# 2A_Regulation_board.net
KiCad netlist of a schematic drawn in EAGLE
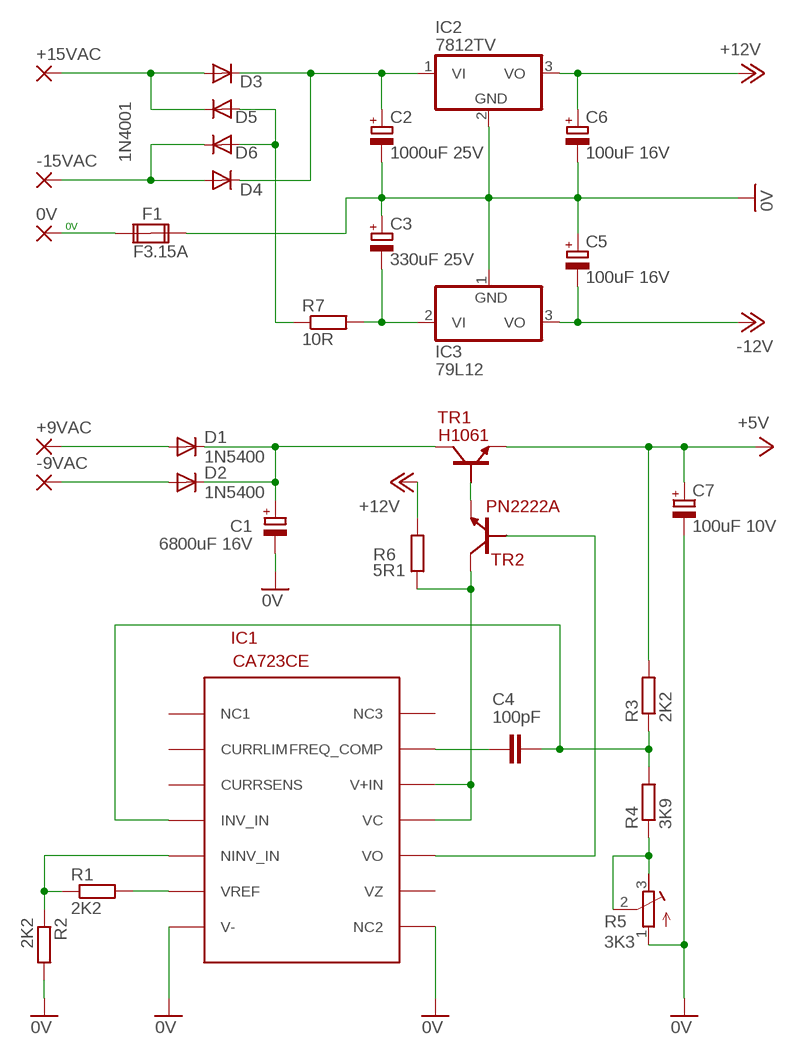
[diagram p0: schematic, sheet 1]

(export (version "E")
  (design (tool "Eeschema 10.0.6"))
  (components
    (comp (ref "+9VAC")
      (value "3,81/1,4")
      (footprint "eagle-import:3,81_1,4")
      (libsource (lib "eagle-import") (part "3,81/1,4"))
    )
    (comp (ref "+15VAC")
      (value "3,81/1,4")
      (footprint "eagle-import:3,81_1,4")
      (libsource (lib "eagle-import") (part "3,81/1,4"))
    )
    (comp (ref "-9VAC")
      (value "3,81/1,4")
      (footprint "eagle-import:3,81_1,4")
      (libsource (lib "eagle-import") (part "3,81/1,4"))
    )
    (comp (ref "-15VAC")
      (value "3,81/1,4")
      (footprint "eagle-import:3,81_1,4")
      (libsource (lib "eagle-import") (part "3,81/1,4"))
    )
    (comp (ref "0V")
      (value "3,81/1,4")
      (footprint "eagle-import:3,81_1,4")
      (libsource (lib "eagle-import") (part "3,81/1,4"))
    )
    (comp (ref "C1")
      (value "6800uF 16V")
      (footprint "eagle-import:E7,5-16")
      (libsource (lib "eagle-import") (part "CPOL-EUE7.5-16"))
    )
    (comp (ref "C2")
      (value "1000uF 25V")
      (footprint "eagle-import:E5-13")
      (libsource (lib "eagle-import") (part "CPOL-EUE5-13"))
    )
    (comp (ref "C3")
      (value "330uF 25V")
      (footprint "eagle-import:E5-10,5")
      (libsource (lib "eagle-import") (part "CPOL-EUE5-10.5"))
    )
    (comp (ref "C4")
      (value "100pF")
      (footprint "eagle-import:C025-025X050")
      (libsource (lib "eagle-import") (part "C-EU025-025X050"))
    )
    (comp (ref "C5")
      (value "100uF 16V")
      (footprint "eagle-import:E2,5-6")
      (libsource (lib "eagle-import") (part "CPOL-EUE2.5-6"))
    )
    (comp (ref "C6")
      (value "100uF 16V")
      (footprint "eagle-import:E2,5-6")
      (libsource (lib "eagle-import") (part "CPOL-EUE2.5-6"))
    )
    (comp (ref "C7")
      (value "100uF 10V")
      (footprint "eagle-import:E2-5")
      (libsource (lib "eagle-import") (part "CPOL-EUE2-5"))
    )
    (comp (ref "D1")
      (value "1N5400")
      (footprint "eagle-import:DO201-15")
      (libsource (lib "eagle-import") (part "1N5400"))
    )
    (comp (ref "D2")
      (value "1N5400")
      (footprint "eagle-import:DO201-15")
      (libsource (lib "eagle-import") (part "1N5400"))
    )
    (comp (ref "D3")
      (value "1N4001")
      (footprint "eagle-import:DO41-10")
      (libsource (lib "eagle-import") (part "1N4004"))
    )
    (comp (ref "D4")
      (value "1N4001")
      (footprint "eagle-import:DO41-10")
      (libsource (lib "eagle-import") (part "1N4004"))
    )
    (comp (ref "D5")
      (value "1N4001")
      (footprint "eagle-import:DO41-10")
      (libsource (lib "eagle-import") (part "1N4004"))
    )
    (comp (ref "D6")
      (value "1N4001")
      (footprint "eagle-import:DO41-10")
      (libsource (lib "eagle-import") (part "1N4004"))
    )
    (comp (ref "F1")
      (value "F3.15A")
      (footprint "eagle-import:FUSE1")
      (libsource (lib "eagle-import") (part "FUSE2P"))
    )
    (comp (ref "IC1")
      (value "CA723CE")
      (footprint "eagle-import:PDIP-14")
      (libsource (lib "eagle-import") (part "CA723CA-PDIP"))
    )
    (comp (ref "IC2")
      (value "7812TV")
      (footprint "eagle-import:TO220V")
      (libsource (lib "eagle-import") (part "78TV12"))
    )
    (comp (ref "IC3")
      (value "79L12")
      (footprint "eagle-import:TO92")
      (libsource (lib "eagle-import") (part "79L12"))
    )
    (comp (ref "R1")
      (value "2K2")
      (footprint "eagle-import:0207_10")
      (libsource (lib "eagle-import") (part "R-EU_0207/10"))
    )
    (comp (ref "R2")
      (value "2K2")
      (footprint "eagle-import:0207_10")
      (libsource (lib "eagle-import") (part "R-EU_0207/10"))
    )
    (comp (ref "R3")
      (value "2K2")
      (footprint "eagle-import:0207_10")
      (libsource (lib "eagle-import") (part "R-EU_0207/10"))
    )
    (comp (ref "R4")
      (value "3K9")
      (footprint "eagle-import:0207_10")
      (libsource (lib "eagle-import") (part "R-EU_0207/10"))
    )
    (comp (ref "R5")
      (value "3K3")
      (footprint "eagle-import:RTRIM3339P")
      (libsource (lib "eagle-import") (part "R-TRIMM3339P"))
    )
    (comp (ref "R6")
      (value "5R1")
      (footprint "eagle-import:0207_15")
      (libsource (lib "eagle-import") (part "R-EU_0207/15"))
    )
    (comp (ref "R7")
      (value "10R")
      (footprint "eagle-import:0309_10")
      (libsource (lib "eagle-import") (part "R-EU_0309/10"))
    )
    (comp (ref "TR1")
      (value "H1061")
      (footprint "eagle-import:TO220AB")
      (libsource (lib "eagle-import") (part "H1061"))
    )
    (comp (ref "TR2")
      (value "PN2222A")
      (footprint "eagle-import:TO-92")
      (libsource (lib "eagle-import") (part "PN2222A"))
    )
  )
  (nets
    (net (code "1") (name "+5V") (class "Default")
      (node (ref "C7") (pin "+") (pinfunction "+_+") (pintype "passive"))
      (node (ref "R3") (pin "2") (pinfunction "2_2") (pintype "passive"))
      (node (ref "TR1") (pin "E") (pinfunction "E_E") (pintype "bidirectional"))
    )
    (net (code "2") (name "+12V") (class "Default")
      (node (ref "C6") (pin "+") (pinfunction "+_+") (pintype "passive"))
      (node (ref "IC2") (pin "3") (pinfunction "VO_3") (pintype "passive"))
      (node (ref "R6") (pin "2") (pinfunction "2_2") (pintype "passive"))
    )
    (net (code "3") (name "-12V") (class "Default")
      (node (ref "C5") (pin "-") (pinfunction "-_-") (pintype "passive"))
      (node (ref "IC3") (pin "3") (pinfunction "VO_3") (pintype "passive"))
    )
    (net (code "4") (name "0V") (class "Default")
      (node (ref "C1") (pin "-") (pinfunction "-_-") (pintype "passive"))
      (node (ref "C2") (pin "-") (pinfunction "-_-") (pintype "passive"))
      (node (ref "C3") (pin "+") (pinfunction "+_+") (pintype "passive"))
      (node (ref "C5") (pin "+") (pinfunction "+_+") (pintype "passive"))
      (node (ref "C6") (pin "-") (pinfunction "-_-") (pintype "passive"))
      (node (ref "C7") (pin "-") (pinfunction "-_-") (pintype "passive"))
      (node (ref "F1") (pin "2A") (pinfunction "2A_2A") (pintype "passive"))
      (node (ref "IC1") (pin "NC2") (pinfunction "NC2_NC2") (pintype "bidirectional"))
      (node (ref "IC1") (pin "V-") (pinfunction "V-_V-") (pintype "bidirectional"))
      (node (ref "IC2") (pin "2") (pinfunction "GND_2") (pintype "passive"))
      (node (ref "IC3") (pin "1") (pinfunction "GND_1") (pintype "passive"))
      (node (ref "R2") (pin "2") (pinfunction "2_2") (pintype "passive"))
      (node (ref "R5") (pin "1") (pinfunction "E_1") (pintype "passive"))
    )
    (net (code "5") (name "Net-(+9VAC-P)") (class "Default")
      (node (ref "+9VAC") (pin "1") (pinfunction "P_1") (pintype "passive"))
      (node (ref "D1") (pin "A") (pinfunction "A_A") (pintype "passive"))
    )
    (net (code "6") (name "Net-(+15VAC-P)") (class "Default")
      (node (ref "+15VAC") (pin "1") (pinfunction "P_1") (pintype "passive"))
      (node (ref "D3") (pin "A") (pinfunction "A_A") (pintype "passive"))
      (node (ref "D5") (pin "C") (pinfunction "C_C") (pintype "passive"))
    )
    (net (code "7") (name "Net-(-9VAC-P)") (class "Default")
      (node (ref "-9VAC") (pin "1") (pinfunction "P_1") (pintype "passive"))
      (node (ref "D2") (pin "A") (pinfunction "A_A") (pintype "passive"))
    )
    (net (code "8") (name "Net-(-15VAC-P)") (class "Default")
      (node (ref "-15VAC") (pin "1") (pinfunction "P_1") (pintype "passive"))
      (node (ref "D4") (pin "A") (pinfunction "A_A") (pintype "passive"))
      (node (ref "D6") (pin "C") (pinfunction "C_C") (pintype "passive"))
    )
    (net (code "9") (name "Net-(0V-P)") (class "Default")
      (node (ref "0V") (pin "1") (pinfunction "P_1") (pintype "passive"))
      (node (ref "F1") (pin "1A") (pinfunction "1A_1A") (pintype "passive"))
    )
    (net (code "10") (name "Net-(C1-Pad+)") (class "Default")
      (node (ref "C1") (pin "+") (pinfunction "+_+") (pintype "passive"))
      (node (ref "D1") (pin "C") (pinfunction "C_C") (pintype "passive"))
      (node (ref "D2") (pin "C") (pinfunction "C_C") (pintype "passive"))
      (node (ref "TR1") (pin "C") (pinfunction "C_C") (pintype "bidirectional"))
    )
    (net (code "11") (name "Net-(C4-Pad1)") (class "Default")
      (node (ref "C4") (pin "1") (pinfunction "1_1") (pintype "passive"))
      (node (ref "IC1") (pin "FREQ_COMP") (pinfunction "FREQ_COMP_FREQ_COMP") (pintype "bidirectional"))
    )
    (net (code "12") (name "Net-(D5-PadA)") (class "Default")
      (node (ref "D5") (pin "A") (pinfunction "A_A") (pintype "passive"))
      (node (ref "D6") (pin "A") (pinfunction "A_A") (pintype "passive"))
      (node (ref "R7") (pin "1") (pinfunction "1_1") (pintype "passive"))
    )
    (net (code "13") (name "Net-(IC1-INV_IN)") (class "Default")
      (node (ref "C4") (pin "2") (pinfunction "2_2") (pintype "passive"))
      (node (ref "IC1") (pin "INV_INP") (pinfunction "INV_IN_INV_INP") (pintype "bidirectional"))
      (node (ref "R3") (pin "1") (pinfunction "1_1") (pintype "passive"))
      (node (ref "R4") (pin "2") (pinfunction "2_2") (pintype "passive"))
    )
    (net (code "14") (name "Net-(IC1-NINV_IN)") (class "Default")
      (node (ref "IC1") (pin "NINV_INP") (pinfunction "NINV_IN_NINV_INP") (pintype "bidirectional"))
      (node (ref "R1") (pin "1") (pinfunction "1_1") (pintype "passive"))
      (node (ref "R2") (pin "1") (pinfunction "1_1") (pintype "passive"))
    )
    (net (code "15") (name "Net-(IC1-PadV+IN)") (class "Default")
      (node (ref "IC1") (pin "V+IN") (pinfunction "V+IN_V+IN") (pintype "bidirectional"))
      (node (ref "IC1") (pin "VC") (pinfunction "VC_VC") (pintype "bidirectional"))
      (node (ref "R6") (pin "1") (pinfunction "1_1") (pintype "passive"))
      (node (ref "TR2") (pin "C") (pinfunction "C_C") (pintype "bidirectional"))
    )
    (net (code "16") (name "Net-(IC1-PadVO)") (class "Default")
      (node (ref "IC1") (pin "VO") (pinfunction "VO_VO") (pintype "bidirectional"))
      (node (ref "TR2") (pin "B") (pinfunction "B_B") (pintype "bidirectional"))
    )
    (net (code "17") (name "Net-(IC1-PadVREF)") (class "Default")
      (node (ref "IC1") (pin "VREF") (pinfunction "VREF_VREF") (pintype "bidirectional"))
      (node (ref "R1") (pin "2") (pinfunction "2_2") (pintype "passive"))
    )
    (net (code "18") (name "Net-(IC2-VI)") (class "Default")
      (node (ref "C2") (pin "+") (pinfunction "+_+") (pintype "passive"))
      (node (ref "D3") (pin "C") (pinfunction "C_C") (pintype "passive"))
      (node (ref "D4") (pin "C") (pinfunction "C_C") (pintype "passive"))
      (node (ref "IC2") (pin "1") (pinfunction "VI_1") (pintype "input"))
    )
    (net (code "19") (name "Net-(IC3-VI)") (class "Default")
      (node (ref "C3") (pin "-") (pinfunction "-_-") (pintype "passive"))
      (node (ref "IC3") (pin "2") (pinfunction "VI_2") (pintype "input"))
      (node (ref "R7") (pin "2") (pinfunction "2_2") (pintype "passive"))
    )
    (net (code "20") (name "Net-(R5-A)") (class "Default")
      (node (ref "R4") (pin "1") (pinfunction "1_1") (pintype "passive"))
      (node (ref "R5") (pin "2") (pinfunction "S_2") (pintype "passive"))
      (node (ref "R5") (pin "3") (pinfunction "A_3") (pintype "passive"))
    )
    (net (code "21") (name "Net-(TR1-PadB)") (class "Default")
      (node (ref "TR1") (pin "B") (pinfunction "B_B") (pintype "bidirectional"))
      (node (ref "TR2") (pin "E") (pinfunction "E_E") (pintype "bidirectional"))
    )
    (net (code "22") (name "unconnected-(F1-Pad1B)") (class "Default")
      (node (ref "F1") (pin "1B") (pinfunction "1B_1B") (pintype "passive"))
    )
    (net (code "23") (name "unconnected-(F1-Pad2B)") (class "Default")
      (node (ref "F1") (pin "2B") (pinfunction "2B_2B") (pintype "passive"))
    )
    (net (code "24") (name "unconnected-(IC1-CURRLIM-PadCURR_LIM)") (class "Default")
      (node (ref "IC1") (pin "CURR_LIM") (pinfunction "CURRLIM_CURR_LIM") (pintype "bidirectional"))
    )
    (net (code "25") (name "unconnected-(IC1-CURRSENS-PadCURR_SENS)") (class "Default")
      (node (ref "IC1") (pin "CURR_SENS") (pinfunction "CURRSENS_CURR_SENS") (pintype "bidirectional"))
    )
    (net (code "26") (name "unconnected-(IC1-PadNC1)") (class "Default")
      (node (ref "IC1") (pin "NC1") (pinfunction "NC1_NC1") (pintype "bidirectional"))
    )
    (net (code "27") (name "unconnected-(IC1-PadNC3)") (class "Default")
      (node (ref "IC1") (pin "NC3") (pinfunction "NC3_NC3") (pintype "bidirectional"))
    )
    (net (code "28") (name "unconnected-(IC1-PadVZ)") (class "Default")
      (node (ref "IC1") (pin "VZ") (pinfunction "VZ_VZ") (pintype "bidirectional"))
    )
  )
)
